# digitboard.net
KiCad netlist of a schematic drawn in EAGLE
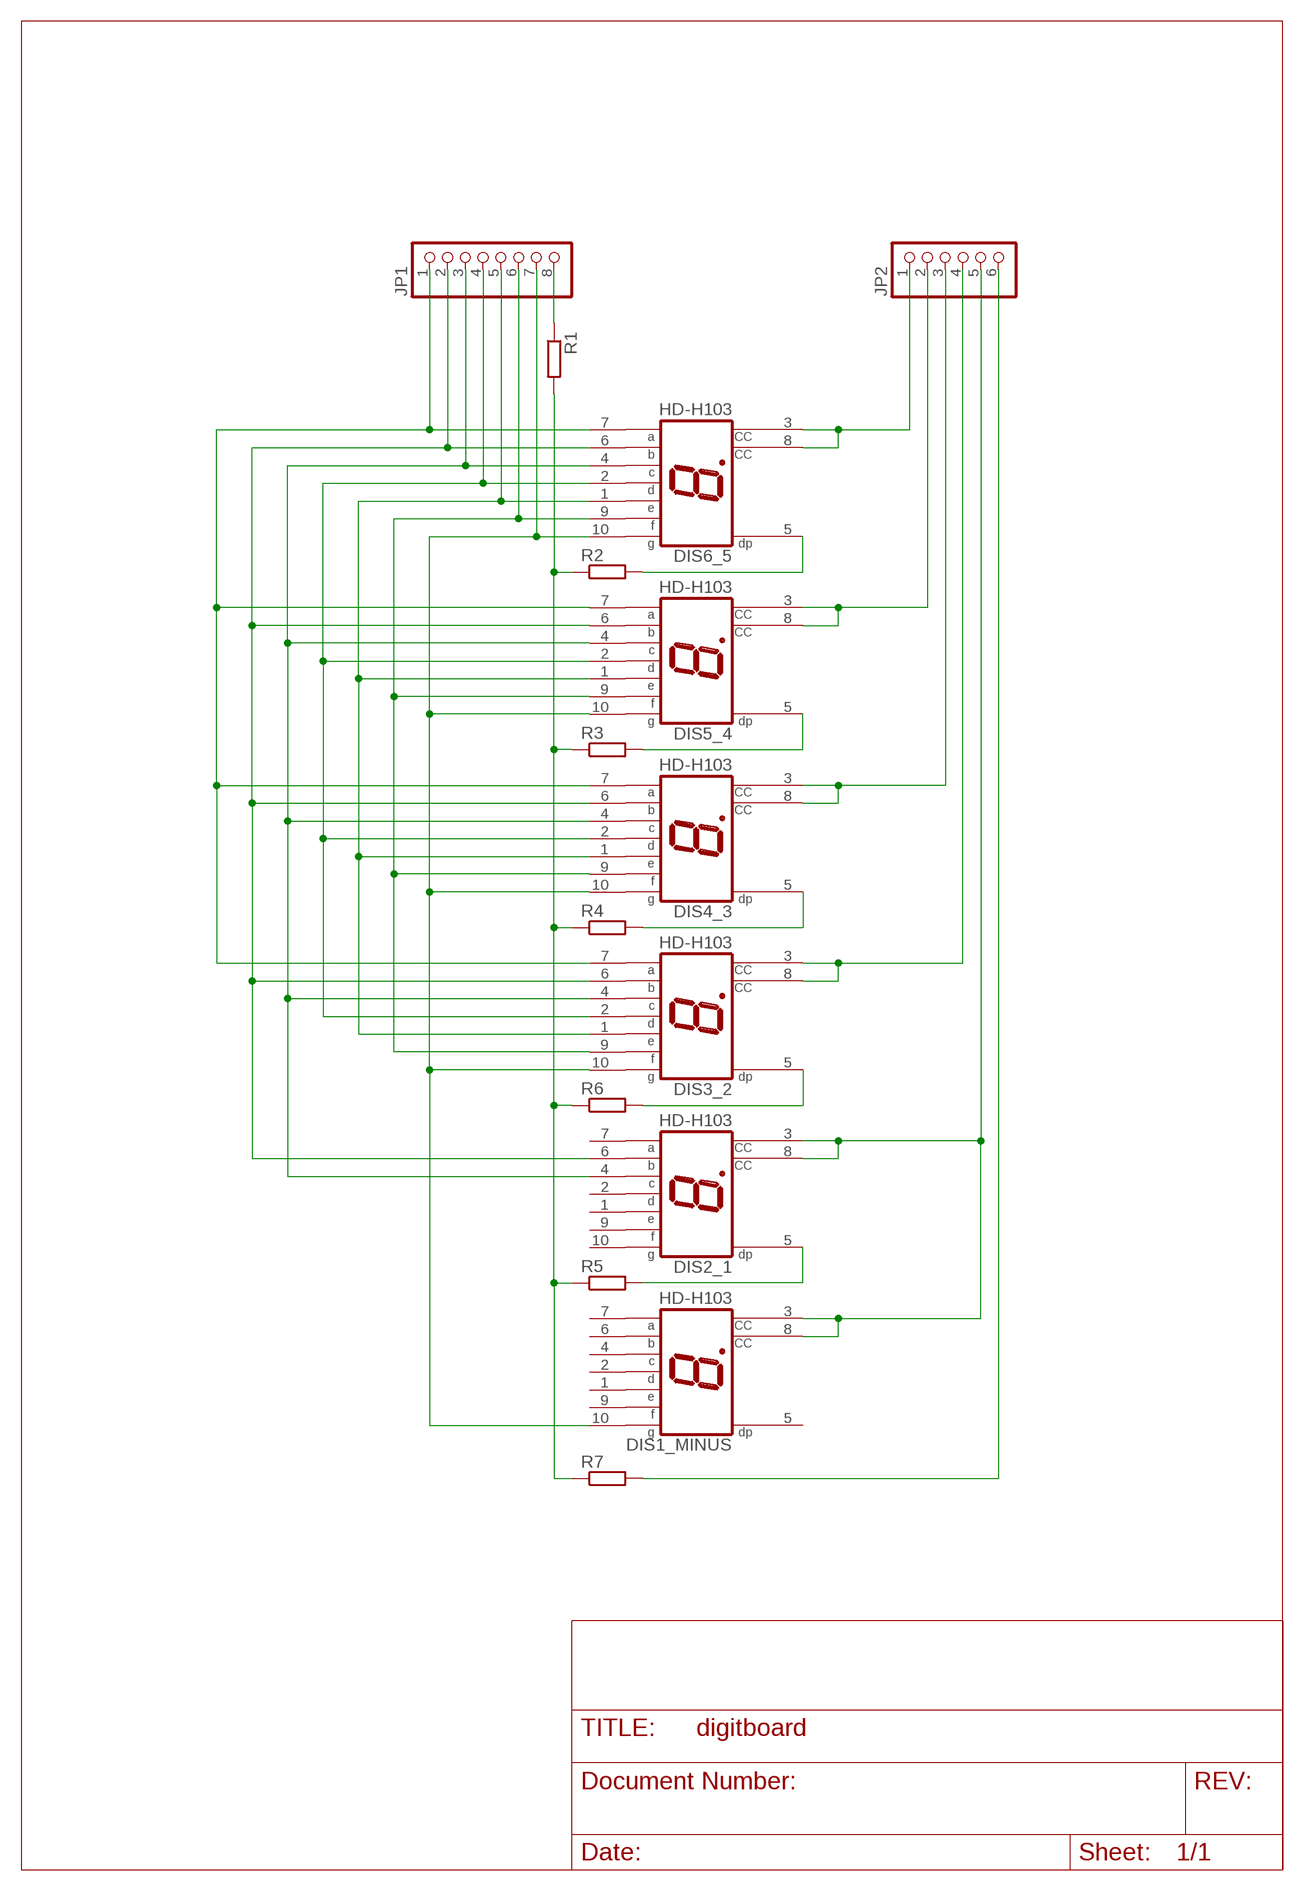
[diagram p0: schematic, sheet 1]

(export (version "E")
  (design (tool "Eeschema 10.0.6"))
  (components
    (comp (ref "DIS1_MINUS")
      (value "HD-H103")
      (footprint "eagle-import:HDSP-M")
      (libsource (lib "eagle-import") (part "HD-H103"))
    )
    (comp (ref "DIS2_1")
      (value "HD-H103")
      (footprint "eagle-import:HDSP-M")
      (libsource (lib "eagle-import") (part "HD-H103"))
    )
    (comp (ref "DIS3_2")
      (value "HD-H103")
      (footprint "eagle-import:HDSP-M")
      (libsource (lib "eagle-import") (part "HD-H103"))
    )
    (comp (ref "DIS4_3")
      (value "HD-H103")
      (footprint "eagle-import:HDSP-M")
      (libsource (lib "eagle-import") (part "HD-H103"))
    )
    (comp (ref "DIS5_4")
      (value "HD-H103")
      (footprint "eagle-import:HDSP-M")
      (libsource (lib "eagle-import") (part "HD-H103"))
    )
    (comp (ref "DIS6_5")
      (value "HD-H103")
      (footprint "eagle-import:HDSP-M")
      (libsource (lib "eagle-import") (part "HD-H103"))
    )
    (comp (ref "JP1")
      (value "PINHD-1X8")
      (footprint "eagle-import:1X08")
      (libsource (lib "eagle-import") (part "PINHD-1X8"))
    )
    (comp (ref "JP2")
      (value "PINHD-1X6")
      (footprint "eagle-import:1X06")
      (libsource (lib "eagle-import") (part "PINHD-1X6"))
    )
    (comp (ref "R1")
      (value "R-EU_R0603")
      (footprint "eagle-import:R0603")
      (libsource (lib "eagle-import") (part "R-EU_R0603"))
    )
    (comp (ref "R2")
      (value "R-EU_R0603")
      (footprint "eagle-import:R0603")
      (libsource (lib "eagle-import") (part "R-EU_R0603"))
    )
    (comp (ref "R3")
      (value "R-EU_R0603")
      (footprint "eagle-import:R0603")
      (libsource (lib "eagle-import") (part "R-EU_R0603"))
    )
    (comp (ref "R4")
      (value "R-EU_R0603")
      (footprint "eagle-import:R0603")
      (libsource (lib "eagle-import") (part "R-EU_R0603"))
    )
    (comp (ref "R5")
      (value "R-EU_R0603")
      (footprint "eagle-import:R0603")
      (libsource (lib "eagle-import") (part "R-EU_R0603"))
    )
    (comp (ref "R6")
      (value "R-EU_R0603")
      (footprint "eagle-import:R0603")
      (libsource (lib "eagle-import") (part "R-EU_R0603"))
    )
    (comp (ref "R7")
      (value "R-EU_R0603")
      (footprint "eagle-import:R0603")
      (libsource (lib "eagle-import") (part "R-EU_R0603"))
    )
  )
  (nets
    (net (code "1") (name "Net-(DIS1_MINUS-CC-Pad3)") (class "Default")
      (node (ref "DIS1_MINUS") (pin "3") (pinfunction "CC_3") (pintype "passive"))
      (node (ref "DIS1_MINUS") (pin "8") (pinfunction "CC_8") (pintype "passive"))
      (node (ref "DIS2_1") (pin "3") (pinfunction "CC_3") (pintype "passive"))
      (node (ref "DIS2_1") (pin "8") (pinfunction "CC_8") (pintype "passive"))
      (node (ref "JP2") (pin "5") (pinfunction "5_5") (pintype "passive"))
    )
    (net (code "2") (name "Net-(DIS1_MINUS-G)") (class "Default")
      (node (ref "DIS1_MINUS") (pin "10") (pinfunction "G_10") (pintype "passive"))
      (node (ref "DIS3_2") (pin "10") (pinfunction "G_10") (pintype "passive"))
      (node (ref "DIS4_3") (pin "10") (pinfunction "G_10") (pintype "passive"))
      (node (ref "DIS5_4") (pin "10") (pinfunction "G_10") (pintype "passive"))
      (node (ref "DIS6_5") (pin "10") (pinfunction "G_10") (pintype "passive"))
      (node (ref "JP1") (pin "7") (pinfunction "7_7") (pintype "passive"))
    )
    (net (code "3") (name "Net-(DIS2_1-B)") (class "Default")
      (node (ref "DIS2_1") (pin "6") (pinfunction "B_6") (pintype "passive"))
      (node (ref "DIS3_2") (pin "6") (pinfunction "B_6") (pintype "passive"))
      (node (ref "DIS4_3") (pin "6") (pinfunction "B_6") (pintype "passive"))
      (node (ref "DIS5_4") (pin "6") (pinfunction "B_6") (pintype "passive"))
      (node (ref "DIS6_5") (pin "6") (pinfunction "B_6") (pintype "passive"))
      (node (ref "JP1") (pin "2") (pinfunction "2_2") (pintype "passive"))
    )
    (net (code "4") (name "Net-(DIS2_1-C)") (class "Default")
      (node (ref "DIS2_1") (pin "4") (pinfunction "C_4") (pintype "passive"))
      (node (ref "DIS3_2") (pin "4") (pinfunction "C_4") (pintype "passive"))
      (node (ref "DIS4_3") (pin "4") (pinfunction "C_4") (pintype "passive"))
      (node (ref "DIS5_4") (pin "4") (pinfunction "C_4") (pintype "passive"))
      (node (ref "DIS6_5") (pin "4") (pinfunction "C_4") (pintype "passive"))
      (node (ref "JP1") (pin "3") (pinfunction "3_3") (pintype "passive"))
    )
    (net (code "5") (name "Net-(DIS2_1-DP)") (class "Default")
      (node (ref "DIS2_1") (pin "5") (pinfunction "DP_5") (pintype "passive"))
      (node (ref "R5") (pin "2") (pinfunction "2_2") (pintype "passive"))
    )
    (net (code "6") (name "Net-(DIS3_2-A)") (class "Default")
      (node (ref "DIS3_2") (pin "7") (pinfunction "A_7") (pintype "passive"))
      (node (ref "DIS4_3") (pin "7") (pinfunction "A_7") (pintype "passive"))
      (node (ref "DIS5_4") (pin "7") (pinfunction "A_7") (pintype "passive"))
      (node (ref "DIS6_5") (pin "7") (pinfunction "A_7") (pintype "passive"))
      (node (ref "JP1") (pin "1") (pinfunction "1_1") (pintype "passive"))
    )
    (net (code "7") (name "Net-(DIS3_2-CC-Pad3)") (class "Default")
      (node (ref "DIS3_2") (pin "3") (pinfunction "CC_3") (pintype "passive"))
      (node (ref "DIS3_2") (pin "8") (pinfunction "CC_8") (pintype "passive"))
      (node (ref "JP2") (pin "4") (pinfunction "4_4") (pintype "passive"))
    )
    (net (code "8") (name "Net-(DIS3_2-D)") (class "Default")
      (node (ref "DIS3_2") (pin "2") (pinfunction "D_2") (pintype "passive"))
      (node (ref "DIS4_3") (pin "2") (pinfunction "D_2") (pintype "passive"))
      (node (ref "DIS5_4") (pin "2") (pinfunction "D_2") (pintype "passive"))
      (node (ref "DIS6_5") (pin "2") (pinfunction "D_2") (pintype "passive"))
      (node (ref "JP1") (pin "4") (pinfunction "4_4") (pintype "passive"))
    )
    (net (code "9") (name "Net-(DIS3_2-DP)") (class "Default")
      (node (ref "DIS3_2") (pin "5") (pinfunction "DP_5") (pintype "passive"))
      (node (ref "R6") (pin "2") (pinfunction "2_2") (pintype "passive"))
    )
    (net (code "10") (name "Net-(DIS3_2-E)") (class "Default")
      (node (ref "DIS3_2") (pin "1") (pinfunction "E_1") (pintype "passive"))
      (node (ref "DIS4_3") (pin "1") (pinfunction "E_1") (pintype "passive"))
      (node (ref "DIS5_4") (pin "1") (pinfunction "E_1") (pintype "passive"))
      (node (ref "DIS6_5") (pin "1") (pinfunction "E_1") (pintype "passive"))
      (node (ref "JP1") (pin "5") (pinfunction "5_5") (pintype "passive"))
    )
    (net (code "11") (name "Net-(DIS3_2-F)") (class "Default")
      (node (ref "DIS3_2") (pin "9") (pinfunction "F_9") (pintype "passive"))
      (node (ref "DIS4_3") (pin "9") (pinfunction "F_9") (pintype "passive"))
      (node (ref "DIS5_4") (pin "9") (pinfunction "F_9") (pintype "passive"))
      (node (ref "DIS6_5") (pin "9") (pinfunction "F_9") (pintype "passive"))
      (node (ref "JP1") (pin "6") (pinfunction "6_6") (pintype "passive"))
    )
    (net (code "12") (name "Net-(DIS4_3-CC-Pad3)") (class "Default")
      (node (ref "DIS4_3") (pin "3") (pinfunction "CC_3") (pintype "passive"))
      (node (ref "DIS4_3") (pin "8") (pinfunction "CC_8") (pintype "passive"))
      (node (ref "JP2") (pin "3") (pinfunction "3_3") (pintype "passive"))
    )
    (net (code "13") (name "Net-(DIS4_3-DP)") (class "Default")
      (node (ref "DIS4_3") (pin "5") (pinfunction "DP_5") (pintype "passive"))
      (node (ref "R4") (pin "2") (pinfunction "2_2") (pintype "passive"))
    )
    (net (code "14") (name "Net-(DIS5_4-CC-Pad3)") (class "Default")
      (node (ref "DIS5_4") (pin "3") (pinfunction "CC_3") (pintype "passive"))
      (node (ref "DIS5_4") (pin "8") (pinfunction "CC_8") (pintype "passive"))
      (node (ref "JP2") (pin "2") (pinfunction "2_2") (pintype "passive"))
    )
    (net (code "15") (name "Net-(DIS5_4-DP)") (class "Default")
      (node (ref "DIS5_4") (pin "5") (pinfunction "DP_5") (pintype "passive"))
      (node (ref "R3") (pin "2") (pinfunction "2_2") (pintype "passive"))
    )
    (net (code "16") (name "Net-(DIS6_5-CC-Pad3)") (class "Default")
      (node (ref "DIS6_5") (pin "3") (pinfunction "CC_3") (pintype "passive"))
      (node (ref "DIS6_5") (pin "8") (pinfunction "CC_8") (pintype "passive"))
      (node (ref "JP2") (pin "1") (pinfunction "1_1") (pintype "passive"))
    )
    (net (code "17") (name "Net-(DIS6_5-DP)") (class "Default")
      (node (ref "DIS6_5") (pin "5") (pinfunction "DP_5") (pintype "passive"))
      (node (ref "R2") (pin "2") (pinfunction "2_2") (pintype "passive"))
    )
    (net (code "18") (name "Net-(JP1-Pad8)") (class "Default")
      (node (ref "JP1") (pin "8") (pinfunction "8_8") (pintype "passive"))
      (node (ref "R1") (pin "1") (pinfunction "1_1") (pintype "passive"))
    )
    (net (code "19") (name "Net-(JP2-Pad6)") (class "Default")
      (node (ref "JP2") (pin "6") (pinfunction "6_6") (pintype "passive"))
      (node (ref "R7") (pin "2") (pinfunction "2_2") (pintype "passive"))
    )
    (net (code "20") (name "Net-(R1-Pad2)") (class "Default")
      (node (ref "R1") (pin "2") (pinfunction "2_2") (pintype "passive"))
      (node (ref "R2") (pin "1") (pinfunction "1_1") (pintype "passive"))
      (node (ref "R3") (pin "1") (pinfunction "1_1") (pintype "passive"))
      (node (ref "R4") (pin "1") (pinfunction "1_1") (pintype "passive"))
      (node (ref "R5") (pin "1") (pinfunction "1_1") (pintype "passive"))
      (node (ref "R6") (pin "1") (pinfunction "1_1") (pintype "passive"))
      (node (ref "R7") (pin "1") (pinfunction "1_1") (pintype "passive"))
    )
    (net (code "21") (name "unconnected-(DIS1_MINUS-A-Pad7)") (class "Default")
      (node (ref "DIS1_MINUS") (pin "7") (pinfunction "A_7") (pintype "passive"))
    )
    (net (code "22") (name "unconnected-(DIS1_MINUS-B-Pad6)") (class "Default")
      (node (ref "DIS1_MINUS") (pin "6") (pinfunction "B_6") (pintype "passive"))
    )
    (net (code "23") (name "unconnected-(DIS1_MINUS-C-Pad4)") (class "Default")
      (node (ref "DIS1_MINUS") (pin "4") (pinfunction "C_4") (pintype "passive"))
    )
    (net (code "24") (name "unconnected-(DIS1_MINUS-D-Pad2)") (class "Default")
      (node (ref "DIS1_MINUS") (pin "2") (pinfunction "D_2") (pintype "passive"))
    )
    (net (code "25") (name "unconnected-(DIS1_MINUS-DP-Pad5)") (class "Default")
      (node (ref "DIS1_MINUS") (pin "5") (pinfunction "DP_5") (pintype "passive"))
    )
    (net (code "26") (name "unconnected-(DIS1_MINUS-E-Pad1)") (class "Default")
      (node (ref "DIS1_MINUS") (pin "1") (pinfunction "E_1") (pintype "passive"))
    )
    (net (code "27") (name "unconnected-(DIS1_MINUS-F-Pad9)") (class "Default")
      (node (ref "DIS1_MINUS") (pin "9") (pinfunction "F_9") (pintype "passive"))
    )
    (net (code "28") (name "unconnected-(DIS2_1-A-Pad7)") (class "Default")
      (node (ref "DIS2_1") (pin "7") (pinfunction "A_7") (pintype "passive"))
    )
    (net (code "29") (name "unconnected-(DIS2_1-D-Pad2)") (class "Default")
      (node (ref "DIS2_1") (pin "2") (pinfunction "D_2") (pintype "passive"))
    )
    (net (code "30") (name "unconnected-(DIS2_1-E-Pad1)") (class "Default")
      (node (ref "DIS2_1") (pin "1") (pinfunction "E_1") (pintype "passive"))
    )
    (net (code "31") (name "unconnected-(DIS2_1-F-Pad9)") (class "Default")
      (node (ref "DIS2_1") (pin "9") (pinfunction "F_9") (pintype "passive"))
    )
    (net (code "32") (name "unconnected-(DIS2_1-G-Pad10)") (class "Default")
      (node (ref "DIS2_1") (pin "10") (pinfunction "G_10") (pintype "passive"))
    )
  )
)
